# splitter.net
KiCad netlist of a schematic drawn in EAGLE
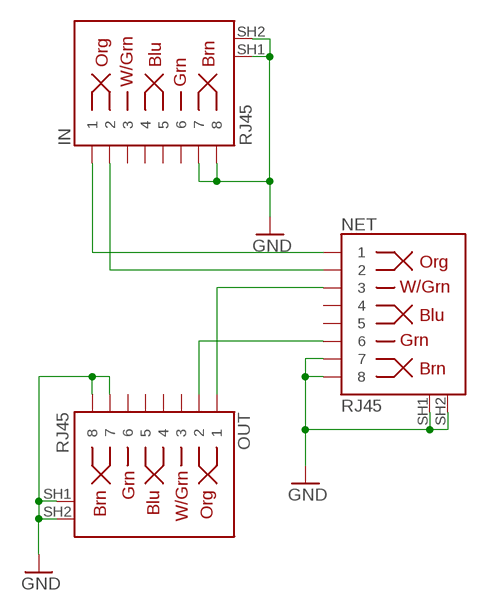
[diagram p0: schematic, sheet 1]

(export (version "E")
  (design (tool "Eeschema 10.0.6"))
  (components
    (comp (ref "IN")
      (value "RJ45")
      (footprint "eagle-import:RJ45-8")
      (libsource (lib "eagle-import") (part "RJ45-8"))
    )
    (comp (ref "NET")
      (value "RJ45")
      (footprint "eagle-import:RJ45-8")
      (libsource (lib "eagle-import") (part "RJ45-8"))
    )
    (comp (ref "OUT")
      (value "RJ45")
      (footprint "eagle-import:RJ45-8")
      (libsource (lib "eagle-import") (part "RJ45-8"))
    )
  )
  (nets
    (net (code "1") (name "GND") (class "Default")
      (node (ref "IN") (pin "7") (pinfunction "7_7") (pintype "bidirectional"))
      (node (ref "IN") (pin "8") (pinfunction "8_8") (pintype "bidirectional"))
      (node (ref "IN") (pin "SH1") (pinfunction "SH1_SH1") (pintype "bidirectional"))
      (node (ref "IN") (pin "SH2") (pinfunction "SH2_SH2") (pintype "bidirectional"))
      (node (ref "NET") (pin "7") (pinfunction "7_7") (pintype "bidirectional"))
      (node (ref "NET") (pin "8") (pinfunction "8_8") (pintype "bidirectional"))
      (node (ref "NET") (pin "SH1") (pinfunction "SH1_SH1") (pintype "bidirectional"))
      (node (ref "NET") (pin "SH2") (pinfunction "SH2_SH2") (pintype "bidirectional"))
      (node (ref "OUT") (pin "7") (pinfunction "7_7") (pintype "bidirectional"))
      (node (ref "OUT") (pin "8") (pinfunction "8_8") (pintype "bidirectional"))
      (node (ref "OUT") (pin "SH1") (pinfunction "SH1_SH1") (pintype "bidirectional"))
      (node (ref "OUT") (pin "SH2") (pinfunction "SH2_SH2") (pintype "bidirectional"))
    )
    (net (code "2") (name "Net-(IN-Pad1)") (class "Default")
      (node (ref "IN") (pin "1") (pinfunction "1_1") (pintype "bidirectional"))
      (node (ref "NET") (pin "1") (pinfunction "1_1") (pintype "bidirectional"))
    )
    (net (code "3") (name "Net-(IN-Pad2)") (class "Default")
      (node (ref "IN") (pin "2") (pinfunction "2_2") (pintype "bidirectional"))
      (node (ref "NET") (pin "2") (pinfunction "2_2") (pintype "bidirectional"))
    )
    (net (code "4") (name "Net-(NET-Pad3)") (class "Default")
      (node (ref "NET") (pin "3") (pinfunction "3_3") (pintype "bidirectional"))
      (node (ref "OUT") (pin "1") (pinfunction "1_1") (pintype "bidirectional"))
    )
    (net (code "5") (name "Net-(NET-Pad6)") (class "Default")
      (node (ref "NET") (pin "6") (pinfunction "6_6") (pintype "bidirectional"))
      (node (ref "OUT") (pin "2") (pinfunction "2_2") (pintype "bidirectional"))
    )
    (net (code "6") (name "unconnected-(IN-Pad3)") (class "Default")
      (node (ref "IN") (pin "3") (pinfunction "3_3") (pintype "bidirectional"))
    )
    (net (code "7") (name "unconnected-(IN-Pad4)") (class "Default")
      (node (ref "IN") (pin "4") (pinfunction "4_4") (pintype "bidirectional"))
    )
    (net (code "8") (name "unconnected-(IN-Pad5)") (class "Default")
      (node (ref "IN") (pin "5") (pinfunction "5_5") (pintype "bidirectional"))
    )
    (net (code "9") (name "unconnected-(IN-Pad6)") (class "Default")
      (node (ref "IN") (pin "6") (pinfunction "6_6") (pintype "bidirectional"))
    )
    (net (code "10") (name "unconnected-(NET-Pad4)") (class "Default")
      (node (ref "NET") (pin "4") (pinfunction "4_4") (pintype "bidirectional"))
    )
    (net (code "11") (name "unconnected-(NET-Pad5)") (class "Default")
      (node (ref "NET") (pin "5") (pinfunction "5_5") (pintype "bidirectional"))
    )
    (net (code "12") (name "unconnected-(OUT-Pad3)") (class "Default")
      (node (ref "OUT") (pin "3") (pinfunction "3_3") (pintype "bidirectional"))
    )
    (net (code "13") (name "unconnected-(OUT-Pad4)") (class "Default")
      (node (ref "OUT") (pin "4") (pinfunction "4_4") (pintype "bidirectional"))
    )
    (net (code "14") (name "unconnected-(OUT-Pad5)") (class "Default")
      (node (ref "OUT") (pin "5") (pinfunction "5_5") (pintype "bidirectional"))
    )
    (net (code "15") (name "unconnected-(OUT-Pad6)") (class "Default")
      (node (ref "OUT") (pin "6") (pinfunction "6_6") (pintype "bidirectional"))
    )
  )
)
